# smpsRev8.net
KiCad netlist of a schematic drawn in EAGLE
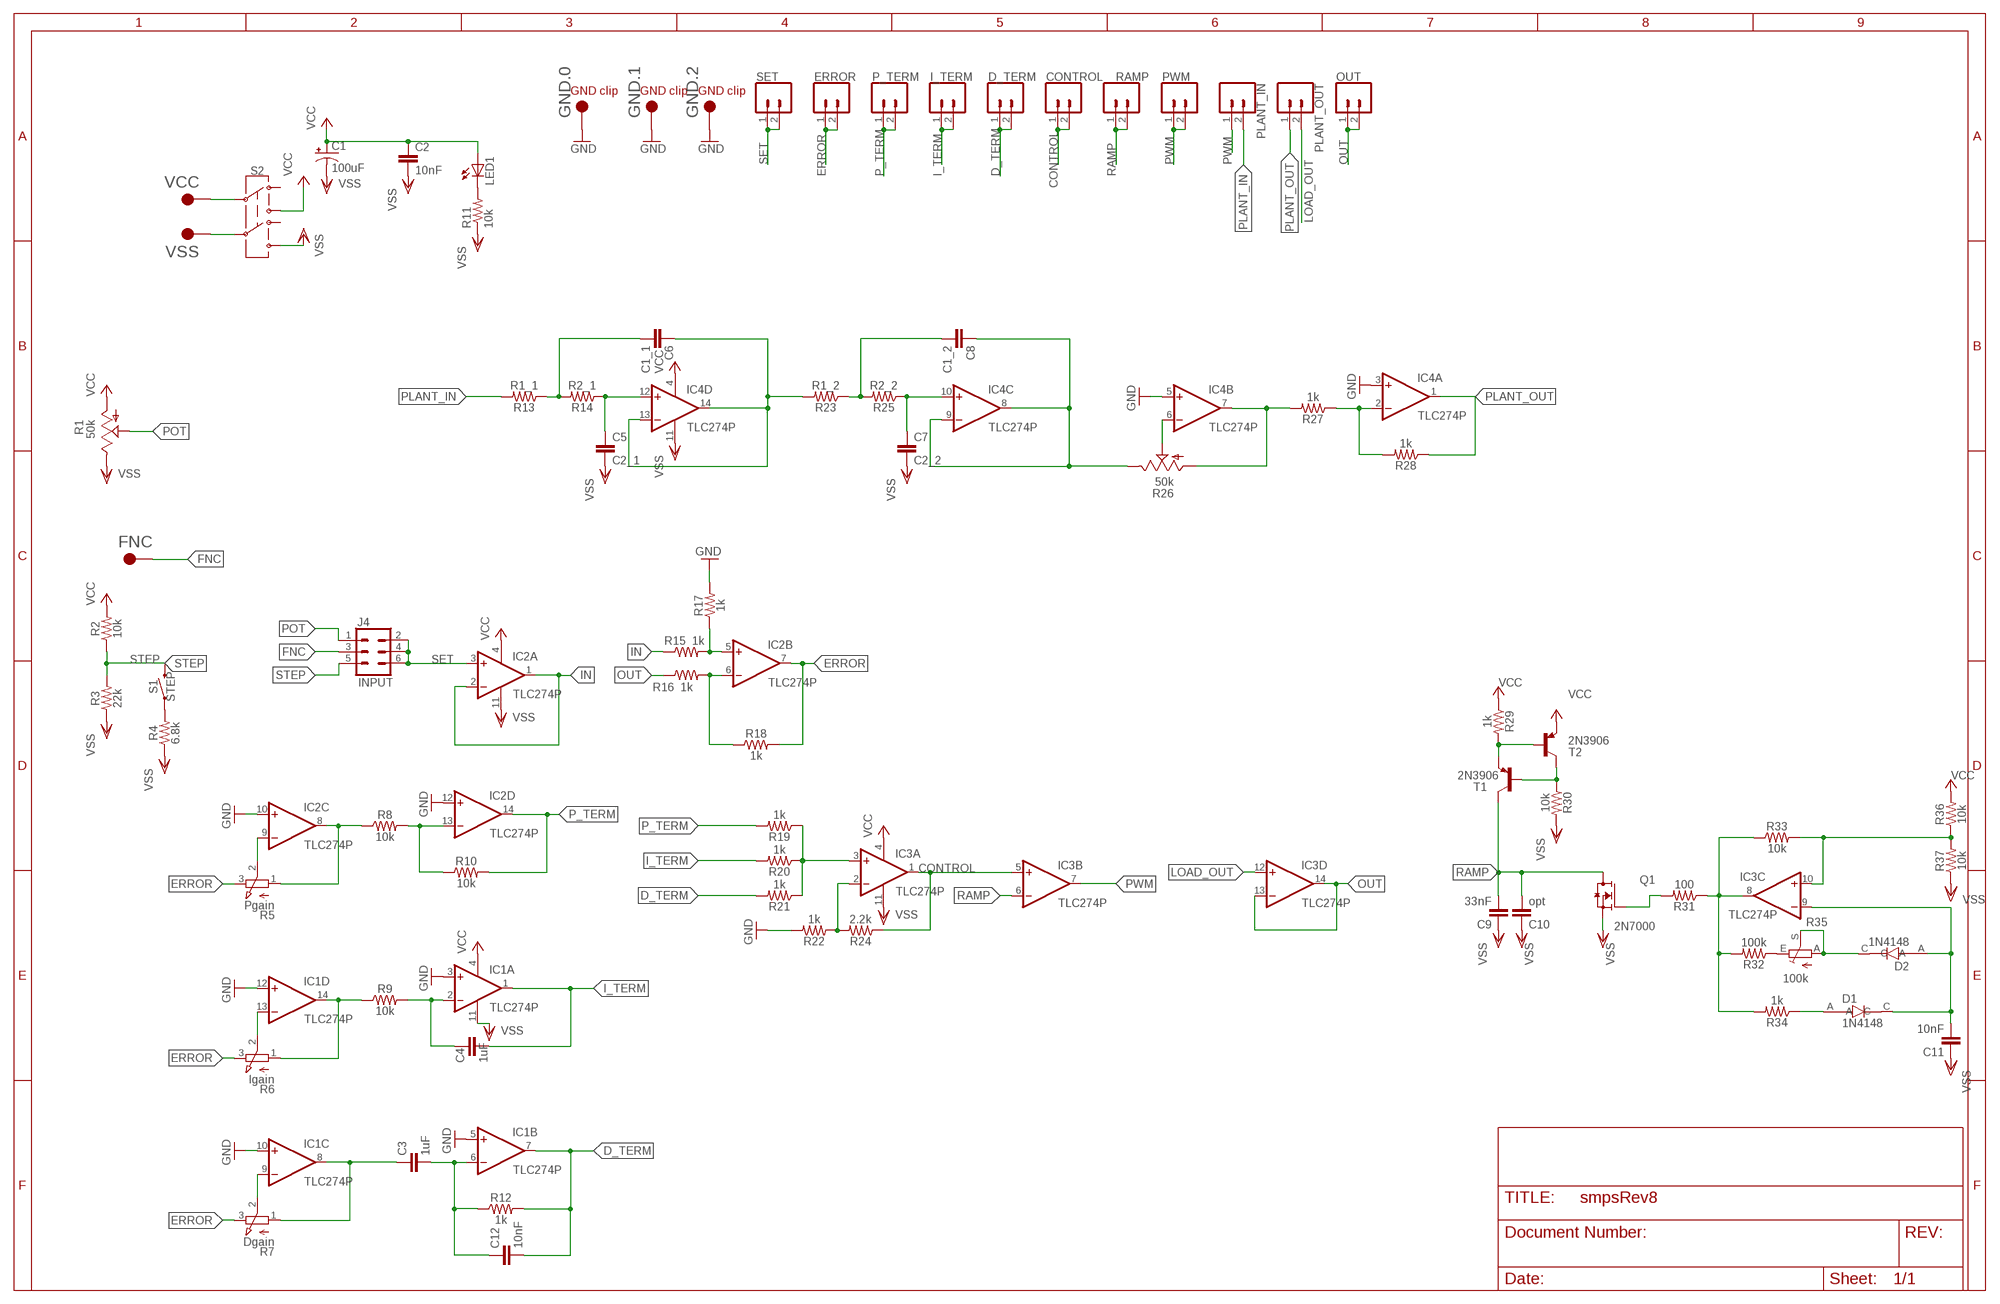
[diagram p0: schematic, sheet 1]

(export (version "E")
  (design (tool "Eeschema 10.0.6"))
  (components
    (comp (ref "C1")
      (value "100uF")
      (footprint "eagle-import:SANYO-OSCON_C")
      (libsource (lib "eagle-import") (part "CPOL-USSANYO_C"))
    )
    (comp (ref "C2")
      (value "10nF")
      (footprint "eagle-import:C1206")
      (libsource (lib "eagle-import") (part "C-EUC1206"))
    )
    (comp (ref "C3")
      (value "1uF")
      (footprint "eagle-import:C1206")
      (libsource (lib "eagle-import") (part "C-EUC1206"))
    )
    (comp (ref "C4")
      (value "1uF")
      (footprint "eagle-import:C1206")
      (libsource (lib "eagle-import") (part "C-EUC1206"))
    )
    (comp (ref "C5")
      (value "C2_1")
      (footprint "eagle-import:C1206")
      (libsource (lib "eagle-import") (part "C-EUC1206"))
    )
    (comp (ref "C6")
      (value "C1_1")
      (footprint "eagle-import:C1206")
      (libsource (lib "eagle-import") (part "C-EUC1206"))
    )
    (comp (ref "C7")
      (value "C2_2")
      (footprint "eagle-import:C1206")
      (libsource (lib "eagle-import") (part "C-EUC1206"))
    )
    (comp (ref "C8")
      (value "C1_2")
      (footprint "eagle-import:C1206")
      (libsource (lib "eagle-import") (part "C-EUC1206"))
    )
    (comp (ref "C9")
      (value "33nF")
      (footprint "eagle-import:C1206")
      (libsource (lib "eagle-import") (part "C-EUC1206"))
    )
    (comp (ref "C10")
      (value "opt")
      (footprint "eagle-import:C050-024X044")
      (libsource (lib "eagle-import") (part "C-EU050-024X044"))
    )
    (comp (ref "C11")
      (value "10nF")
      (footprint "eagle-import:C1206")
      (libsource (lib "eagle-import") (part "C-EUC1206"))
    )
    (comp (ref "C12")
      (value "10nF")
      (footprint "eagle-import:C1206")
      (libsource (lib "eagle-import") (part "C-EUC1206"))
    )
    (comp (ref "CONTROL")
      (value "CONN_02LOCK")
      (footprint "eagle-import:1X02_LOCK")
      (libsource (lib "eagle-import") (part "CONN_02LOCK"))
    )
    (comp (ref "D1")
      (value "1N4148")
      (footprint "eagle-import:SOD2513X120N")
      (fields (field (name "MANUFACTURER") "Diodes Inc."))
      (libsource (lib "eagle-import") (part "1N4148WS-7-F"))
    )
    (comp (ref "D2")
      (value "1N4148")
      (footprint "eagle-import:SOD2513X120N")
      (fields (field (name "MANUFACTURER") "Diodes Inc."))
      (libsource (lib "eagle-import") (part "1N4148WS-7-F"))
    )
    (comp (ref "D_TERM")
      (value "CONN_02LOCK")
      (footprint "eagle-import:1X02_LOCK")
      (libsource (lib "eagle-import") (part "CONN_02LOCK"))
    )
    (comp (ref "ERROR")
      (value "CONN_02LOCK")
      (footprint "eagle-import:1X02_LOCK")
      (libsource (lib "eagle-import") (part "CONN_02LOCK"))
    )
    (comp (ref "FNC")
      (value "5016")
      (footprint "eagle-import:KEYSTONE_5016")
      (fields (field (name "MANUFACTURER") "Keystone Electronics"))
      (libsource (lib "eagle-import") (part "5016"))
    )
    (comp (ref "GND.0")
      (value "5016")
      (footprint "eagle-import:KEYSTONE_5016")
      (fields (field (name "MANUFACTURER") "Keystone Electronics"))
      (libsource (lib "eagle-import") (part "5016"))
    )
    (comp (ref "GND.1")
      (value "5016")
      (footprint "eagle-import:KEYSTONE_5016")
      (fields (field (name "MANUFACTURER") "Keystone Electronics"))
      (libsource (lib "eagle-import") (part "5016"))
    )
    (comp (ref "GND.2")
      (value "5016")
      (footprint "eagle-import:KEYSTONE_5016")
      (fields (field (name "MANUFACTURER") "Keystone Electronics"))
      (libsource (lib "eagle-import") (part "5016"))
    )
    (comp (ref "IC1")
      (value "TLC274P")
      (footprint "eagle-import:DIL14")
      (libsource (lib "eagle-import") (part "TLC274P"))
    )
    (comp (ref "IC2")
      (value "TLC274P")
      (footprint "eagle-import:DIL14")
      (libsource (lib "eagle-import") (part "TLC274P"))
    )
    (comp (ref "IC3")
      (value "TLC274P")
      (footprint "eagle-import:DIL14")
      (libsource (lib "eagle-import") (part "linear_262_TLC274P"))
    )
    (comp (ref "IC4")
      (value "TLC274P")
      (footprint "eagle-import:DIL14")
      (libsource (lib "eagle-import") (part "TLC274P"))
    )
    (comp (ref "I_TERM")
      (value "CONN_02LOCK")
      (footprint "eagle-import:1X02_LOCK")
      (libsource (lib "eagle-import") (part "CONN_02LOCK"))
    )
    (comp (ref "J4")
      (value "INPUT")
      (footprint "eagle-import:2X3")
      (libsource (lib "eagle-import") (part "CONN_03X2FEMALE"))
    )
    (comp (ref "LED1")
      (value "LEDCHIPLED_1206")
      (footprint "eagle-import:CHIPLED_1206")
      (libsource (lib "eagle-import") (part "LEDCHIPLED_1206"))
    )
    (comp (ref "OUT")
      (value "CONN_02LOCK")
      (footprint "eagle-import:1X02_LOCK")
      (libsource (lib "eagle-import") (part "CONN_02LOCK"))
    )
    (comp (ref "PLANT_IN")
      (value "CONN_02LOCK")
      (footprint "eagle-import:1X02_LOCK")
      (libsource (lib "eagle-import") (part "CONN_02LOCK"))
    )
    (comp (ref "PLANT_OUT")
      (value "CONN_02LOCK")
      (footprint "eagle-import:1X02_LOCK")
      (libsource (lib "eagle-import") (part "CONN_02LOCK"))
    )
    (comp (ref "PWM")
      (value "CONN_02LOCK")
      (footprint "eagle-import:1X02_LOCK")
      (libsource (lib "eagle-import") (part "CONN_02LOCK"))
    )
    (comp (ref "P_TERM")
      (value "CONN_02LOCK")
      (footprint "eagle-import:1X02_LOCK")
      (libsource (lib "eagle-import") (part "CONN_02LOCK"))
    )
    (comp (ref "Q1")
      (value "2N7000")
      (footprint "eagle-import:TO92254P458H750-3")
      (fields (field (name "MANUFACTURER") "Diotec Semiconductor"))
      (libsource (lib "eagle-import") (part "2N7000"))
    )
    (comp (ref "R1")
      (value "50k")
      (footprint "eagle-import:B25P")
      (libsource (lib "eagle-import") (part "TRIM_US-B25P"))
    )
    (comp (ref "R2")
      (value "10k")
      (footprint "eagle-import:1206")
      (libsource (lib "eagle-import") (part "RESISTOR1206"))
    )
    (comp (ref "R3")
      (value "22k")
      (footprint "eagle-import:1206")
      (libsource (lib "eagle-import") (part "RESISTOR1206"))
    )
    (comp (ref "R4")
      (value "6.8k")
      (footprint "eagle-import:1206")
      (libsource (lib "eagle-import") (part "RESISTOR1206"))
    )
    (comp (ref "R5")
      (value "Pgain")
      (footprint "eagle-import:EVUF")
      (libsource (lib "eagle-import") (part "EVUAF2"))
    )
    (comp (ref "R6")
      (value "Igain")
      (footprint "eagle-import:EVUF")
      (libsource (lib "eagle-import") (part "EVUAF2"))
    )
    (comp (ref "R7")
      (value "Dgain")
      (footprint "eagle-import:EVUF")
      (libsource (lib "eagle-import") (part "EVUAF2"))
    )
    (comp (ref "R8")
      (value "10k")
      (footprint "eagle-import:1206")
      (libsource (lib "eagle-import") (part "RESISTOR1206"))
    )
    (comp (ref "R9")
      (value "10k")
      (footprint "eagle-import:1206")
      (libsource (lib "eagle-import") (part "RESISTOR1206"))
    )
    (comp (ref "R10")
      (value "10k")
      (footprint "eagle-import:1206")
      (libsource (lib "eagle-import") (part "RESISTOR1206"))
    )
    (comp (ref "R11")
      (value "10k")
      (footprint "eagle-import:R1206")
      (libsource (lib "eagle-import") (part "R-US_R1206"))
    )
    (comp (ref "R12")
      (value "1k")
      (footprint "eagle-import:1206")
      (libsource (lib "eagle-import") (part "RESISTOR1206"))
    )
    (comp (ref "R13")
      (value "R1_1")
      (footprint "eagle-import:1206")
      (libsource (lib "eagle-import") (part "RESISTOR1206"))
    )
    (comp (ref "R14")
      (value "R2_1")
      (footprint "eagle-import:1206")
      (libsource (lib "eagle-import") (part "RESISTOR1206"))
    )
    (comp (ref "R15")
      (value "1k")
      (footprint "eagle-import:1206")
      (libsource (lib "eagle-import") (part "RESISTOR1206"))
    )
    (comp (ref "R16")
      (value "1k")
      (footprint "eagle-import:1206")
      (libsource (lib "eagle-import") (part "RESISTOR1206"))
    )
    (comp (ref "R17")
      (value "1k")
      (footprint "eagle-import:1206")
      (libsource (lib "eagle-import") (part "RESISTOR1206"))
    )
    (comp (ref "R18")
      (value "1k")
      (footprint "eagle-import:1206")
      (libsource (lib "eagle-import") (part "RESISTOR1206"))
    )
    (comp (ref "R19")
      (value "1k")
      (footprint "eagle-import:1206")
      (libsource (lib "eagle-import") (part "RESISTOR1206"))
    )
    (comp (ref "R20")
      (value "1k")
      (footprint "eagle-import:1206")
      (libsource (lib "eagle-import") (part "RESISTOR1206"))
    )
    (comp (ref "R21")
      (value "1k")
      (footprint "eagle-import:1206")
      (libsource (lib "eagle-import") (part "RESISTOR1206"))
    )
    (comp (ref "R22")
      (value "1k")
      (footprint "eagle-import:1206")
      (libsource (lib "eagle-import") (part "RESISTOR1206"))
    )
    (comp (ref "R23")
      (value "R1_2")
      (footprint "eagle-import:1206")
      (libsource (lib "eagle-import") (part "RESISTOR1206"))
    )
    (comp (ref "R24")
      (value "2.2k")
      (footprint "eagle-import:1206")
      (libsource (lib "eagle-import") (part "RESISTOR1206"))
    )
    (comp (ref "R25")
      (value "R2_2")
      (footprint "eagle-import:1206")
      (libsource (lib "eagle-import") (part "RESISTOR1206"))
    )
    (comp (ref "R26")
      (value "50k")
      (footprint "eagle-import:B25P")
      (libsource (lib "eagle-import") (part "TRIM_US-B25P"))
    )
    (comp (ref "R27")
      (value "1k")
      (footprint "eagle-import:1206")
      (libsource (lib "eagle-import") (part "RESISTOR1206"))
    )
    (comp (ref "R28")
      (value "1k")
      (footprint "eagle-import:1206")
      (libsource (lib "eagle-import") (part "RESISTOR1206"))
    )
    (comp (ref "R29")
      (value "1k")
      (footprint "eagle-import:1206")
      (libsource (lib "eagle-import") (part "RESISTOR1206"))
    )
    (comp (ref "R30")
      (value "10k")
      (footprint "eagle-import:1206")
      (libsource (lib "eagle-import") (part "RESISTOR1206"))
    )
    (comp (ref "R31")
      (value "100")
      (footprint "eagle-import:1206")
      (libsource (lib "eagle-import") (part "RESISTOR1206"))
    )
    (comp (ref "R32")
      (value "100k")
      (footprint "eagle-import:1206")
      (libsource (lib "eagle-import") (part "RESISTOR1206"))
    )
    (comp (ref "R33")
      (value "10k")
      (footprint "eagle-import:1206")
      (libsource (lib "eagle-import") (part "RESISTOR1206"))
    )
    (comp (ref "R34")
      (value "1k")
      (footprint "eagle-import:1206")
      (libsource (lib "eagle-import") (part "RESISTOR1206"))
    )
    (comp (ref "R35")
      (value "100k")
      (footprint "eagle-import:S64W")
      (libsource (lib "eagle-import") (part "TRIM_EU-S64W"))
    )
    (comp (ref "R36")
      (value "10k")
      (footprint "eagle-import:1206")
      (libsource (lib "eagle-import") (part "RESISTOR1206"))
    )
    (comp (ref "R37")
      (value "10k")
      (footprint "eagle-import:1206")
      (libsource (lib "eagle-import") (part "RESISTOR1206"))
    )
    (comp (ref "RAMP")
      (value "CONN_02LOCK")
      (footprint "eagle-import:1X02_LOCK")
      (libsource (lib "eagle-import") (part "CONN_02LOCK"))
    )
    (comp (ref "S1")
      (value "STEP")
      (footprint "eagle-import:TACTILE_SWITCH_SMD_5.2MM")
      (libsource (lib "eagle-import") (part "MOMENTARY-SWITCH-SPST-SMD-5.2MM"))
    )
    (comp (ref "S2")
      (value "SWITCH-DPDT-SMD-AYZ0202")
      (footprint "eagle-import:SWITCH_DPDT_SMD_AYZ0202")
      (libsource (lib "eagle-import") (part "SWITCH-DPDT-SMD-AYZ0202"))
    )
    (comp (ref "SET")
      (value "CONN_02LOCK")
      (footprint "eagle-import:1X02_LOCK")
      (libsource (lib "eagle-import") (part "CONN_02LOCK"))
    )
    (comp (ref "T1")
      (value "2N3906")
      (footprint "eagle-import:TO92-EBC")
      (libsource (lib "eagle-import") (part "-PNP-TO92-EBC2N3906"))
    )
    (comp (ref "T2")
      (value "2N3906")
      (footprint "eagle-import:TO92-EBC")
      (libsource (lib "eagle-import") (part "-PNP-TO92-EBC2N3906"))
    )
    (comp (ref "VCC")
      (value "5016")
      (footprint "eagle-import:KEYSTONE_5016")
      (fields (field (name "MANUFACTURER") "Keystone Electronics"))
      (libsource (lib "eagle-import") (part "5016"))
    )
    (comp (ref "VSS")
      (value "5016")
      (footprint "eagle-import:KEYSTONE_5016")
      (fields (field (name "MANUFACTURER") "Keystone Electronics"))
      (libsource (lib "eagle-import") (part "5016"))
    )
  )
  (nets
    (net (code "1") (name "/CONTROL") (class "Default")
      (node (ref "CONTROL") (pin "1") (pinfunction "1_1") (pintype "passive"))
      (node (ref "CONTROL") (pin "2") (pinfunction "2_2") (pintype "passive"))
      (node (ref "IC3") (pin "1") (pinfunction "OUT_1") (pintype "output"))
      (node (ref "IC3") (pin "5") (pinfunction "+IN_5") (pintype "input"))
      (node (ref "R24") (pin "1") (pinfunction "1_1") (pintype "passive"))
    )
    (net (code "2") (name "/SET") (class "Default")
      (node (ref "IC2") (pin "3") (pinfunction "+IN_3") (pintype "input"))
      (node (ref "J4") (pin "2") (pinfunction "2_2") (pintype "bidirectional"))
      (node (ref "J4") (pin "4") (pinfunction "4_4") (pintype "bidirectional"))
      (node (ref "J4") (pin "6") (pinfunction "6_6") (pintype "bidirectional"))
      (node (ref "SET") (pin "1") (pinfunction "1_1") (pintype "passive"))
      (node (ref "SET") (pin "2") (pinfunction "2_2") (pintype "passive"))
    )
    (net (code "3") (name "D_TERM") (class "Default")
      (node (ref "C12") (pin "2") (pinfunction "2_2") (pintype "passive"))
      (node (ref "D_TERM") (pin "1") (pinfunction "1_1") (pintype "passive"))
      (node (ref "D_TERM") (pin "2") (pinfunction "2_2") (pintype "passive"))
      (node (ref "IC1") (pin "7") (pinfunction "OUT_7") (pintype "output"))
      (node (ref "R12") (pin "2") (pinfunction "2_2") (pintype "passive"))
      (node (ref "R21") (pin "2") (pinfunction "2_2") (pintype "passive"))
    )
    (net (code "4") (name "ERROR") (class "Default")
      (node (ref "ERROR") (pin "1") (pinfunction "1_1") (pintype "passive"))
      (node (ref "ERROR") (pin "2") (pinfunction "2_2") (pintype "passive"))
      (node (ref "IC2") (pin "7") (pinfunction "OUT_7") (pintype "output"))
      (node (ref "R18") (pin "2") (pinfunction "2_2") (pintype "passive"))
      (node (ref "R5") (pin "3") (pinfunction "E_3") (pintype "passive"))
      (node (ref "R6") (pin "3") (pinfunction "E_3") (pintype "passive"))
      (node (ref "R7") (pin "3") (pinfunction "E_3") (pintype "passive"))
    )
    (net (code "5") (name "FNC") (class "Default")
      (node (ref "FNC") (pin "TP") (pinfunction "TP_TP") (pintype "passive"))
      (node (ref "J4") (pin "3") (pinfunction "3_3") (pintype "bidirectional"))
    )
    (net (code "6") (name "GND") (class "Default")
      (node (ref "GND.0") (pin "TP") (pinfunction "TP_TP") (pintype "passive"))
      (node (ref "GND.1") (pin "TP") (pinfunction "TP_TP") (pintype "passive"))
      (node (ref "GND.2") (pin "TP") (pinfunction "TP_TP") (pintype "passive"))
      (node (ref "IC1") (pin "10") (pinfunction "+IN_10") (pintype "input"))
      (node (ref "IC1") (pin "12") (pinfunction "+IN_12") (pintype "input"))
      (node (ref "IC1") (pin "3") (pinfunction "+IN_3") (pintype "input"))
      (node (ref "IC1") (pin "5") (pinfunction "+IN_5") (pintype "input"))
      (node (ref "IC2") (pin "10") (pinfunction "+IN_10") (pintype "input"))
      (node (ref "IC2") (pin "12") (pinfunction "+IN_12") (pintype "input"))
      (node (ref "IC4") (pin "3") (pinfunction "+IN_3") (pintype "input"))
      (node (ref "IC4") (pin "5") (pinfunction "+IN_5") (pintype "input"))
      (node (ref "R17") (pin "2") (pinfunction "2_2") (pintype "passive"))
      (node (ref "R22") (pin "2") (pinfunction "2_2") (pintype "passive"))
    )
    (net (code "7") (name "IN") (class "Default")
      (node (ref "IC2") (pin "1") (pinfunction "OUT_1") (pintype "output"))
      (node (ref "IC2") (pin "2") (pinfunction "-IN_2") (pintype "input"))
      (node (ref "R15") (pin "1") (pinfunction "1_1") (pintype "passive"))
    )
    (net (code "8") (name "I_TERM") (class "Default")
      (node (ref "C4") (pin "2") (pinfunction "2_2") (pintype "passive"))
      (node (ref "IC1") (pin "1") (pinfunction "OUT_1") (pintype "output"))
      (node (ref "I_TERM") (pin "1") (pinfunction "1_1") (pintype "passive"))
      (node (ref "I_TERM") (pin "2") (pinfunction "2_2") (pintype "passive"))
      (node (ref "R20") (pin "2") (pinfunction "2_2") (pintype "passive"))
    )
    (net (code "9") (name "LOAD_OUT") (class "Default")
      (node (ref "IC3") (pin "12") (pinfunction "+IN_12") (pintype "input"))
      (node (ref "PLANT_OUT") (pin "2") (pinfunction "2_2") (pintype "passive"))
    )
    (net (code "10") (name "Net-(C6-Pad2)") (class "Default")
      (node (ref "C6") (pin "2") (pinfunction "2_2") (pintype "passive"))
      (node (ref "R13") (pin "1") (pinfunction "1_1") (pintype "passive"))
      (node (ref "R14") (pin "2") (pinfunction "2_2") (pintype "passive"))
    )
    (net (code "11") (name "Net-(C8-Pad2)") (class "Default")
      (node (ref "C8") (pin "2") (pinfunction "2_2") (pintype "passive"))
      (node (ref "R23") (pin "1") (pinfunction "1_1") (pintype "passive"))
      (node (ref "R25") (pin "2") (pinfunction "2_2") (pintype "passive"))
    )
    (net (code "12") (name "Net-(D1-PadA)") (class "Default")
      (node (ref "D1") (pin "A") (pinfunction "A_A") (pintype "passive"))
      (node (ref "R34") (pin "1") (pinfunction "1_1") (pintype "passive"))
    )
    (net (code "13") (name "Net-(D2-PadC)") (class "Default")
      (node (ref "D2") (pin "C") (pinfunction "C_C") (pintype "passive"))
      (node (ref "R35") (pin "A") (pinfunction "A_A") (pintype "passive"))
      (node (ref "R35") (pin "S") (pinfunction "S_S") (pintype "passive"))
    )
    (net (code "14") (name "Net-(IC1A--IN)") (class "Default")
      (node (ref "C4") (pin "1") (pinfunction "1_1") (pintype "passive"))
      (node (ref "IC1") (pin "2") (pinfunction "-IN_2") (pintype "input"))
      (node (ref "R9") (pin "2") (pinfunction "2_2") (pintype "passive"))
    )
    (net (code "15") (name "Net-(IC1B--IN)") (class "Default")
      (node (ref "C12") (pin "1") (pinfunction "1_1") (pintype "passive"))
      (node (ref "C3") (pin "2") (pinfunction "2_2") (pintype "passive"))
      (node (ref "IC1") (pin "6") (pinfunction "-IN_6") (pintype "input"))
      (node (ref "R12") (pin "1") (pinfunction "1_1") (pintype "passive"))
    )
    (net (code "16") (name "Net-(IC1C--IN)") (class "Default")
      (node (ref "IC1") (pin "9") (pinfunction "-IN_9") (pintype "input"))
      (node (ref "R7") (pin "2") (pinfunction "S_2") (pintype "passive"))
    )
    (net (code "17") (name "Net-(IC1C-OUT)") (class "Default")
      (node (ref "C3") (pin "1") (pinfunction "1_1") (pintype "passive"))
      (node (ref "IC1") (pin "8") (pinfunction "OUT_8") (pintype "output"))
      (node (ref "R7") (pin "1") (pinfunction "A_1") (pintype "passive"))
    )
    (net (code "18") (name "Net-(IC1D--IN)") (class "Default")
      (node (ref "IC1") (pin "13") (pinfunction "-IN_13") (pintype "input"))
      (node (ref "R6") (pin "2") (pinfunction "S_2") (pintype "passive"))
    )
    (net (code "19") (name "Net-(IC1D-OUT)") (class "Default")
      (node (ref "IC1") (pin "14") (pinfunction "OUT_14") (pintype "output"))
      (node (ref "R6") (pin "1") (pinfunction "A_1") (pintype "passive"))
      (node (ref "R9") (pin "1") (pinfunction "1_1") (pintype "passive"))
    )
    (net (code "20") (name "Net-(IC2B-+IN)") (class "Default")
      (node (ref "IC2") (pin "5") (pinfunction "+IN_5") (pintype "input"))
      (node (ref "R15") (pin "2") (pinfunction "2_2") (pintype "passive"))
      (node (ref "R17") (pin "1") (pinfunction "1_1") (pintype "passive"))
    )
    (net (code "21") (name "Net-(IC2B--IN)") (class "Default")
      (node (ref "IC2") (pin "6") (pinfunction "-IN_6") (pintype "input"))
      (node (ref "R16") (pin "2") (pinfunction "2_2") (pintype "passive"))
      (node (ref "R18") (pin "1") (pinfunction "1_1") (pintype "passive"))
    )
    (net (code "22") (name "Net-(IC2C--IN)") (class "Default")
      (node (ref "IC2") (pin "9") (pinfunction "-IN_9") (pintype "input"))
      (node (ref "R5") (pin "2") (pinfunction "S_2") (pintype "passive"))
    )
    (net (code "23") (name "Net-(IC2C-OUT)") (class "Default")
      (node (ref "IC2") (pin "8") (pinfunction "OUT_8") (pintype "output"))
      (node (ref "R5") (pin "1") (pinfunction "A_1") (pintype "passive"))
      (node (ref "R8") (pin "1") (pinfunction "1_1") (pintype "passive"))
    )
    (net (code "24") (name "Net-(IC2D--IN)") (class "Default")
      (node (ref "IC2") (pin "13") (pinfunction "-IN_13") (pintype "input"))
      (node (ref "R10") (pin "1") (pinfunction "1_1") (pintype "passive"))
      (node (ref "R8") (pin "2") (pinfunction "2_2") (pintype "passive"))
    )
    (net (code "25") (name "Net-(IC3A-+IN)") (class "Default")
      (node (ref "IC3") (pin "3") (pinfunction "+IN_3") (pintype "input"))
      (node (ref "R19") (pin "1") (pinfunction "1_1") (pintype "passive"))
      (node (ref "R20") (pin "1") (pinfunction "1_1") (pintype "passive"))
      (node (ref "R21") (pin "1") (pinfunction "1_1") (pintype "passive"))
    )
    (net (code "26") (name "Net-(IC3A--IN)") (class "Default")
      (node (ref "IC3") (pin "2") (pinfunction "-IN_2") (pintype "input"))
      (node (ref "R22") (pin "1") (pinfunction "1_1") (pintype "passive"))
      (node (ref "R24") (pin "2") (pinfunction "2_2") (pintype "passive"))
    )
    (net (code "27") (name "Net-(IC3C-+IN)") (class "Default")
      (node (ref "IC3") (pin "10") (pinfunction "+IN_10") (pintype "input"))
      (node (ref "R33") (pin "2") (pinfunction "2_2") (pintype "passive"))
      (node (ref "R36") (pin "1") (pinfunction "1_1") (pintype "passive"))
      (node (ref "R37") (pin "2") (pinfunction "2_2") (pintype "passive"))
    )
    (net (code "28") (name "Net-(IC3C--IN)") (class "Default")
      (node (ref "C11") (pin "2") (pinfunction "2_2") (pintype "passive"))
      (node (ref "D1") (pin "C") (pinfunction "C_C") (pintype "passive"))
      (node (ref "D2") (pin "A") (pinfunction "A_A") (pintype "passive"))
      (node (ref "IC3") (pin "9") (pinfunction "-IN_9") (pintype "input"))
    )
    (net (code "29") (name "Net-(IC3C-OUT)") (class "Default")
      (node (ref "IC3") (pin "8") (pinfunction "OUT_8") (pintype "output"))
      (node (ref "R31") (pin "1") (pinfunction "1_1") (pintype "passive"))
      (node (ref "R32") (pin "2") (pinfunction "2_2") (pintype "passive"))
      (node (ref "R33") (pin "1") (pinfunction "1_1") (pintype "passive"))
      (node (ref "R34") (pin "2") (pinfunction "2_2") (pintype "passive"))
    )
    (net (code "30") (name "Net-(IC4A--IN)") (class "Default")
      (node (ref "IC4") (pin "2") (pinfunction "-IN_2") (pintype "input"))
      (node (ref "R27") (pin "1") (pinfunction "1_1") (pintype "passive"))
      (node (ref "R28") (pin "2") (pinfunction "2_2") (pintype "passive"))
    )
    (net (code "31") (name "Net-(IC4B--IN)") (class "Default")
      (node (ref "IC4") (pin "6") (pinfunction "-IN_6") (pintype "input"))
      (node (ref "R26") (pin "S") (pinfunction "S_S") (pintype "passive"))
    )
    (net (code "32") (name "Net-(IC4B-OUT)") (class "Default")
      (node (ref "IC4") (pin "7") (pinfunction "OUT_7") (pintype "output"))
      (node (ref "R26") (pin "A") (pinfunction "A_A") (pintype "passive"))
      (node (ref "R27") (pin "2") (pinfunction "2_2") (pintype "passive"))
    )
    (net (code "33") (name "Net-(IC4C-+IN)") (class "Default")
      (node (ref "C7") (pin "1") (pinfunction "1_1") (pintype "passive"))
      (node (ref "IC4") (pin "10") (pinfunction "+IN_10") (pintype "input"))
      (node (ref "R25") (pin "1") (pinfunction "1_1") (pintype "passive"))
    )
    (net (code "34") (name "Net-(IC4C--IN)") (class "Default")
      (node (ref "C8") (pin "1") (pinfunction "1_1") (pintype "passive"))
      (node (ref "IC4") (pin "8") (pinfunction "OUT_8") (pintype "output"))
      (node (ref "IC4") (pin "9") (pinfunction "-IN_9") (pintype "input"))
      (node (ref "R26") (pin "E") (pinfunction "E_E") (pintype "passive"))
    )
    (net (code "35") (name "Net-(IC4D-+IN)") (class "Default")
      (node (ref "C5") (pin "1") (pinfunction "1_1") (pintype "passive"))
      (node (ref "IC4") (pin "12") (pinfunction "+IN_12") (pintype "input"))
      (node (ref "R14") (pin "1") (pinfunction "1_1") (pintype "passive"))
    )
    (net (code "36") (name "Net-(IC4D--IN)") (class "Default")
      (node (ref "C6") (pin "1") (pinfunction "1_1") (pintype "passive"))
      (node (ref "IC4") (pin "13") (pinfunction "-IN_13") (pintype "input"))
      (node (ref "IC4") (pin "14") (pinfunction "OUT_14") (pintype "output"))
      (node (ref "R23") (pin "2") (pinfunction "2_2") (pintype "passive"))
    )
    (net (code "37") (name "Net-(LED1-PadC)") (class "Default")
      (node (ref "LED1") (pin "C") (pinfunction "C_C") (pintype "passive"))
      (node (ref "R11") (pin "2") (pinfunction "2_2") (pintype "passive"))
    )
    (net (code "38") (name "Net-(Q1-G)") (class "Default")
      (node (ref "Q1") (pin "2") (pinfunction "G_2") (pintype "passive"))
      (node (ref "R31") (pin "2") (pinfunction "2_2") (pintype "passive"))
    )
    (net (code "39") (name "Net-(R4-Pad2)") (class "Default")
      (node (ref "R4") (pin "2") (pinfunction "2_2") (pintype "passive"))
      (node (ref "S1") (pin "1") (pinfunction "1_1") (pintype "passive"))
    )
    (net (code "40") (name "Net-(R29-Pad2)") (class "Default")
      (node (ref "R29") (pin "2") (pinfunction "2_2") (pintype "passive"))
      (node (ref "T1") (pin "E") (pinfunction "E_E") (pintype "passive"))
      (node (ref "T2") (pin "B") (pinfunction "B_B") (pintype "passive"))
    )
    (net (code "41") (name "Net-(R30-Pad1)") (class "Default")
      (node (ref "R30") (pin "1") (pinfunction "1_1") (pintype "passive"))
      (node (ref "T1") (pin "B") (pinfunction "B_B") (pintype "passive"))
      (node (ref "T2") (pin "C") (pinfunction "C_C") (pintype "passive"))
    )
    (net (code "42") (name "Net-(R32-Pad1)") (class "Default")
      (node (ref "R32") (pin "1") (pinfunction "1_1") (pintype "passive"))
      (node (ref "R35") (pin "E") (pinfunction "E_E") (pintype "passive"))
    )
    (net (code "43") (name "Net-(S2-Pad2)") (class "Default")
      (node (ref "S2") (pin "2") (pinfunction "2_2") (pintype "bidirectional"))
      (node (ref "VCC") (pin "TP") (pinfunction "TP_TP") (pintype "passive"))
    )
    (net (code "44") (name "Net-(S2-Pad5)") (class "Default")
      (node (ref "S2") (pin "5") (pinfunction "5_5") (pintype "bidirectional"))
      (node (ref "VSS") (pin "TP") (pinfunction "TP_TP") (pintype "passive"))
    )
    (net (code "45") (name "OUT") (class "Default")
      (node (ref "IC3") (pin "13") (pinfunction "-IN_13") (pintype "input"))
      (node (ref "IC3") (pin "14") (pinfunction "OUT_14") (pintype "output"))
      (node (ref "OUT") (pin "1") (pinfunction "1_1") (pintype "passive"))
      (node (ref "OUT") (pin "2") (pinfunction "2_2") (pintype "passive"))
      (node (ref "R16") (pin "1") (pinfunction "1_1") (pintype "passive"))
    )
    (net (code "46") (name "PLANT_IN") (class "Default")
      (node (ref "PLANT_IN") (pin "2") (pinfunction "2_2") (pintype "passive"))
      (node (ref "R13") (pin "2") (pinfunction "2_2") (pintype "passive"))
    )
    (net (code "47") (name "PLANT_OUT") (class "Default")
      (node (ref "IC4") (pin "1") (pinfunction "OUT_1") (pintype "output"))
      (node (ref "PLANT_OUT") (pin "1") (pinfunction "1_1") (pintype "passive"))
      (node (ref "R28") (pin "1") (pinfunction "1_1") (pintype "passive"))
    )
    (net (code "48") (name "POT") (class "Default")
      (node (ref "J4") (pin "1") (pinfunction "1_1") (pintype "bidirectional"))
      (node (ref "R1") (pin "S") (pinfunction "S_S") (pintype "passive"))
    )
    (net (code "49") (name "PWM") (class "Default")
      (node (ref "IC3") (pin "7") (pinfunction "OUT_7") (pintype "output"))
      (node (ref "PLANT_IN") (pin "1") (pinfunction "1_1") (pintype "passive"))
      (node (ref "PWM") (pin "1") (pinfunction "1_1") (pintype "passive"))
      (node (ref "PWM") (pin "2") (pinfunction "2_2") (pintype "passive"))
    )
    (net (code "50") (name "P_TERM") (class "Default")
      (node (ref "IC2") (pin "14") (pinfunction "OUT_14") (pintype "output"))
      (node (ref "P_TERM") (pin "1") (pinfunction "1_1") (pintype "passive"))
      (node (ref "P_TERM") (pin "2") (pinfunction "2_2") (pintype "passive"))
      (node (ref "R10") (pin "2") (pinfunction "2_2") (pintype "passive"))
      (node (ref "R19") (pin "2") (pinfunction "2_2") (pintype "passive"))
    )
    (net (code "51") (name "RAMP") (class "Default")
      (node (ref "C10") (pin "2") (pinfunction "2_2") (pintype "passive"))
      (node (ref "C9") (pin "2") (pinfunction "2_2") (pintype "passive"))
      (node (ref "IC3") (pin "6") (pinfunction "-IN_6") (pintype "input"))
      (node (ref "Q1") (pin "3") (pinfunction "D_3") (pintype "passive"))
      (node (ref "RAMP") (pin "1") (pinfunction "1_1") (pintype "passive"))
      (node (ref "RAMP") (pin "2") (pinfunction "2_2") (pintype "passive"))
      (node (ref "T1") (pin "C") (pinfunction "C_C") (pintype "passive"))
    )
    (net (code "52") (name "STEP") (class "Default")
      (node (ref "J4") (pin "5") (pinfunction "5_5") (pintype "bidirectional"))
      (node (ref "R2") (pin "1") (pinfunction "1_1") (pintype "passive"))
      (node (ref "R3") (pin "2") (pinfunction "2_2") (pintype "passive"))
      (node (ref "S1") (pin "3") (pinfunction "2_3") (pintype "passive"))
    )
    (net (code "53") (name "VCC") (class "Default")
      (node (ref "C1") (pin "+") (pinfunction "+_+") (pintype "passive"))
      (node (ref "C2") (pin "1") (pinfunction "1_1") (pintype "passive"))
      (node (ref "IC1") (pin "4") (pinfunction "V+_4") (pintype "power_in"))
      (node (ref "IC2") (pin "4") (pinfunction "V+_4") (pintype "power_in"))
      (node (ref "IC3") (pin "4") (pinfunction "V+_4") (pintype "power_in"))
      (node (ref "IC4") (pin "4") (pinfunction "V+_4") (pintype "power_in"))
      (node (ref "LED1") (pin "A") (pinfunction "A_A") (pintype "passive"))
      (node (ref "R1") (pin "A") (pinfunction "A_A") (pintype "passive"))
      (node (ref "R2") (pin "2") (pinfunction "2_2") (pintype "passive"))
      (node (ref "R29") (pin "1") (pinfunction "1_1") (pintype "passive"))
      (node (ref "R36") (pin "2") (pinfunction "2_2") (pintype "passive"))
      (node (ref "S2") (pin "3") (pinfunction "3_3") (pintype "bidirectional"))
      (node (ref "T2") (pin "E") (pinfunction "E_E") (pintype "passive"))
    )
    (net (code "54") (name "VSS") (class "Default")
      (node (ref "C1") (pin "-") (pinfunction "-_-") (pintype "passive"))
      (node (ref "C10") (pin "1") (pinfunction "1_1") (pintype "passive"))
      (node (ref "C11") (pin "1") (pinfunction "1_1") (pintype "passive"))
      (node (ref "C2") (pin "2") (pinfunction "2_2") (pintype "passive"))
      (node (ref "C5") (pin "2") (pinfunction "2_2") (pintype "passive"))
      (node (ref "C7") (pin "2") (pinfunction "2_2") (pintype "passive"))
      (node (ref "C9") (pin "1") (pinfunction "1_1") (pintype "passive"))
      (node (ref "IC1") (pin "11") (pinfunction "V-_11") (pintype "power_in"))
      (node (ref "IC2") (pin "11") (pinfunction "V-_11") (pintype "power_in"))
      (node (ref "IC3") (pin "11") (pinfunction "V-_11") (pintype "power_in"))
      (node (ref "IC4") (pin "11") (pinfunction "V-_11") (pintype "power_in"))
      (node (ref "Q1") (pin "1") (pinfunction "S_1") (pintype "passive"))
      (node (ref "R1") (pin "E") (pinfunction "E_E") (pintype "passive"))
      (node (ref "R11") (pin "1") (pinfunction "1_1") (pintype "passive"))
      (node (ref "R3") (pin "1") (pinfunction "1_1") (pintype "passive"))
      (node (ref "R30") (pin "2") (pinfunction "2_2") (pintype "passive"))
      (node (ref "R37") (pin "1") (pinfunction "1_1") (pintype "passive"))
      (node (ref "R4") (pin "1") (pinfunction "1_1") (pintype "passive"))
      (node (ref "S2") (pin "6") (pinfunction "6_6") (pintype "bidirectional"))
    )
    (net (code "55") (name "unconnected-(S2-Pad1)") (class "Default")
      (node (ref "S2") (pin "1") (pinfunction "1_1") (pintype "bidirectional"))
    )
    (net (code "56") (name "unconnected-(S2-Pad4)") (class "Default")
      (node (ref "S2") (pin "4") (pinfunction "4_4") (pintype "bidirectional"))
    )
  )
)
